# pcb10_13.net
KiCad netlist of a schematic drawn in EAGLE
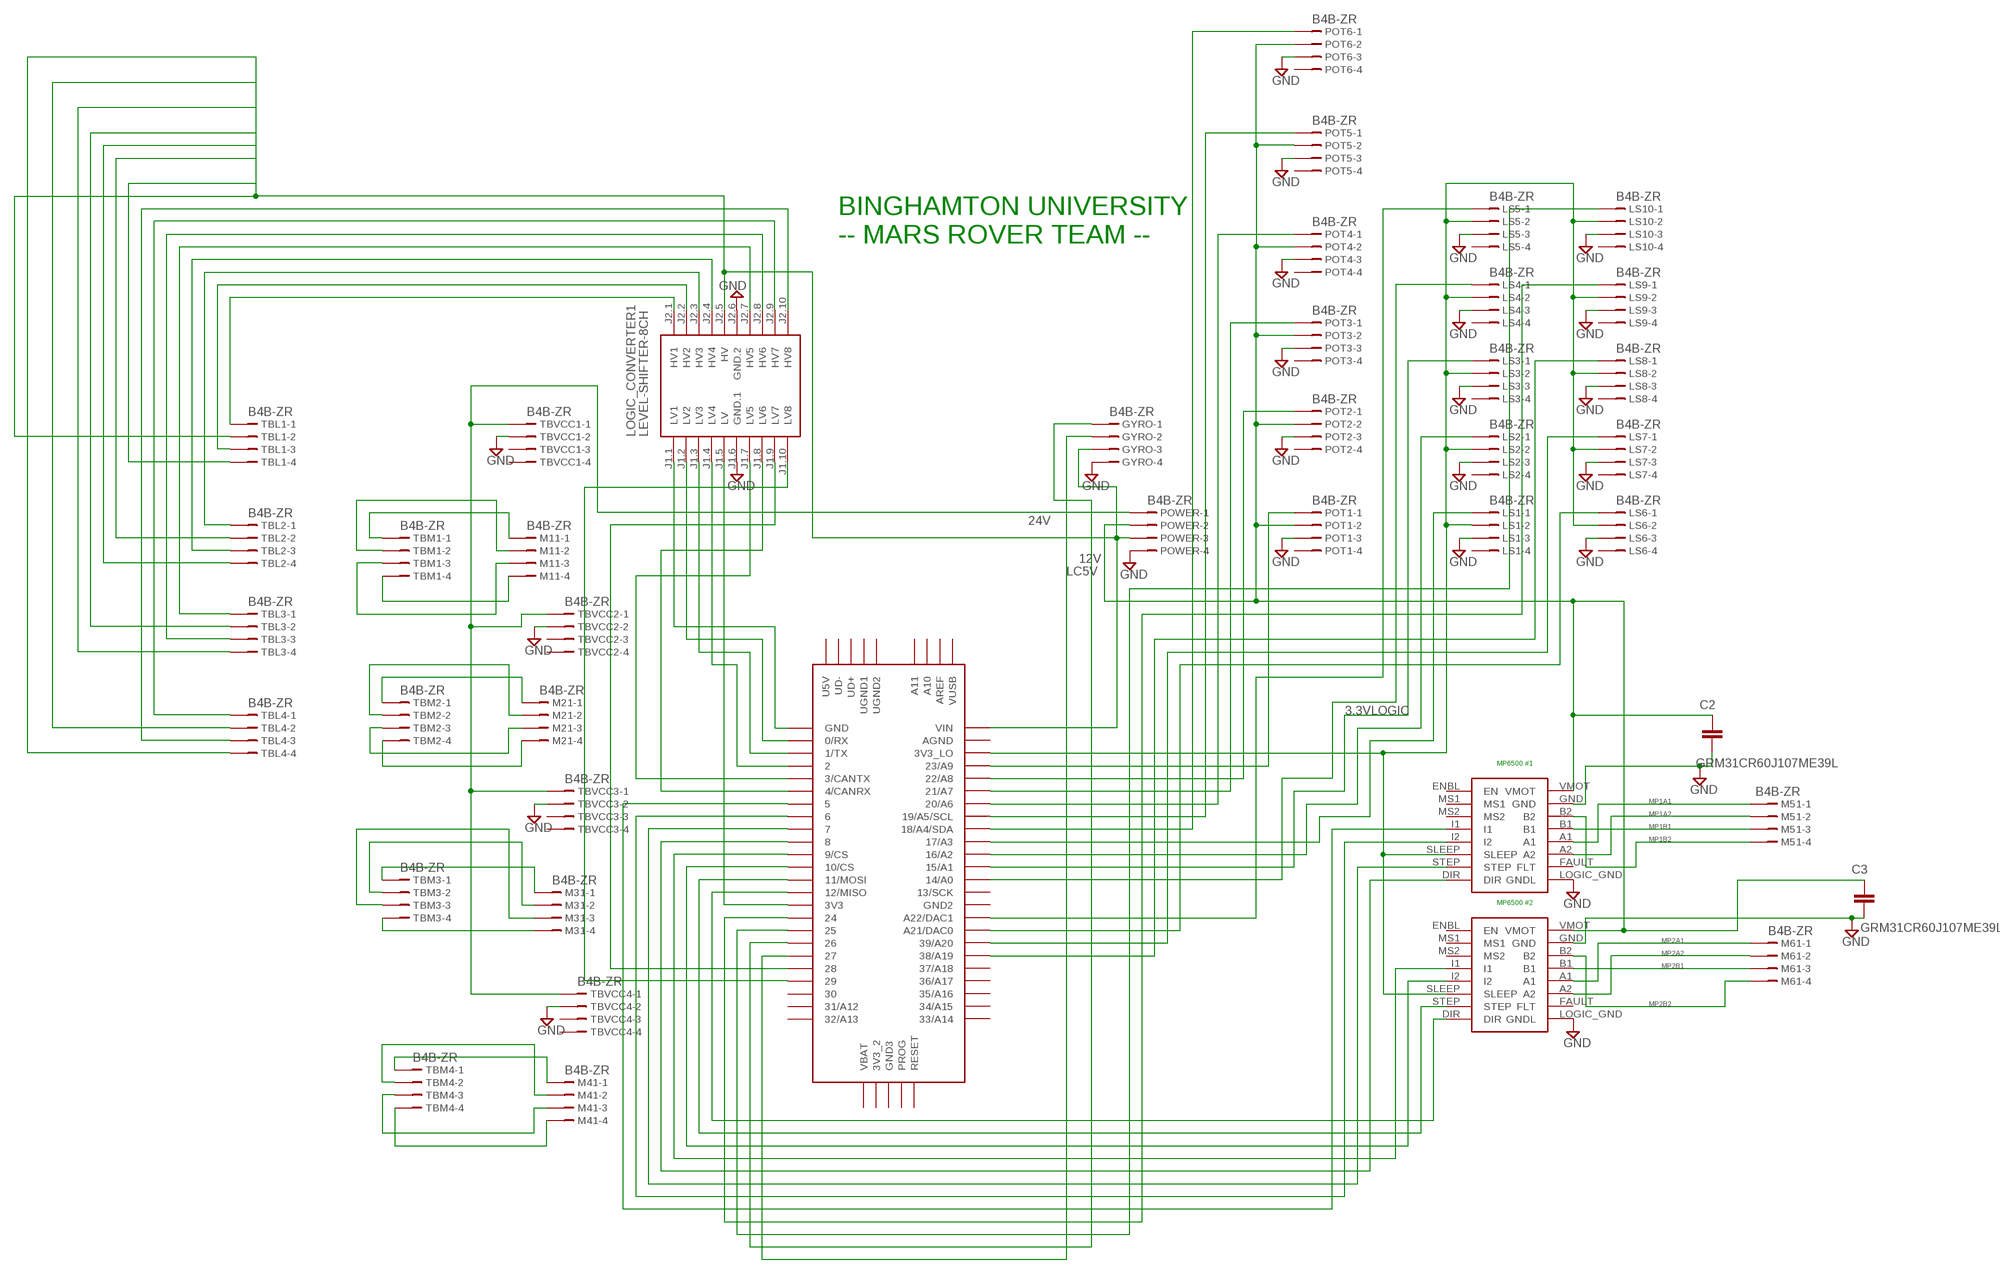
[diagram p0: schematic, sheet 1]

(export (version "E")
  (design (tool "Eeschema 10.0.6"))
  (components
    (comp (ref "C2")
      (value "GRM31CR60J107ME39L")
      (footprint "eagle-import:CAP_1206")
      (fields
        (field (name "MANUFACTURER") "Murata Electronics North America")
        (field (name "CREATED_BY") "PCBLayout.com")
      )
      (libsource (lib "eagle-import") (part "GRM31CR60J107ME39L"))
    )
    (comp (ref "C3")
      (value "GRM31CR60J107ME39L")
      (footprint "eagle-import:CAP_1206")
      (fields
        (field (name "MANUFACTURER") "Murata Electronics North America")
        (field (name "CREATED_BY") "PCBLayout.com")
      )
      (libsource (lib "eagle-import") (part "GRM31CR60J107ME39L"))
    )
    (comp (ref "GYRO")
      (value "B4B-ZR")
      (footprint "eagle-import:B4B-ZR")
      (fields (field (name "MF") "FARNELL") (field (name "MPN") "B4B-ZR(LF)(SN)"))
      (libsource (lib "eagle-import") (part "?4B-ZRB"))
    )
    (comp (ref "LOGIC_CONVERTER1")
      (value "LEVEL-SHIFTER-8CH")
      (footprint "eagle-import:LEVEL-SHIFTER-8CH")
      (libsource (lib "eagle-import") (part "LEVEL-SHIFTER-8CH"))
    )
    (comp (ref "LS1")
      (value "B4B-ZR")
      (footprint "eagle-import:B4B-ZR")
      (fields (field (name "MF") "FARNELL") (field (name "MPN") "B4B-ZR(LF)(SN)"))
      (libsource (lib "eagle-import") (part "?4B-ZRB"))
    )
    (comp (ref "LS2")
      (value "B4B-ZR")
      (footprint "eagle-import:B4B-ZR")
      (fields (field (name "MF") "FARNELL") (field (name "MPN") "B4B-ZR(LF)(SN)"))
      (libsource (lib "eagle-import") (part "?4B-ZRB"))
    )
    (comp (ref "LS3")
      (value "B4B-ZR")
      (footprint "eagle-import:B4B-ZR")
      (fields (field (name "MF") "FARNELL") (field (name "MPN") "B4B-ZR(LF)(SN)"))
      (libsource (lib "eagle-import") (part "?4B-ZRB"))
    )
    (comp (ref "LS4")
      (value "B4B-ZR")
      (footprint "eagle-import:B4B-ZR")
      (fields (field (name "MF") "FARNELL") (field (name "MPN") "B4B-ZR(LF)(SN)"))
      (libsource (lib "eagle-import") (part "?4B-ZRB"))
    )
    (comp (ref "LS5")
      (value "B4B-ZR")
      (footprint "eagle-import:B4B-ZR")
      (fields (field (name "MF") "FARNELL") (field (name "MPN") "B4B-ZR(LF)(SN)"))
      (libsource (lib "eagle-import") (part "?4B-ZRB"))
    )
    (comp (ref "LS6")
      (value "B4B-ZR")
      (footprint "eagle-import:B4B-ZR")
      (fields (field (name "MF") "FARNELL") (field (name "MPN") "B4B-ZR(LF)(SN)"))
      (libsource (lib "eagle-import") (part "?4B-ZRB"))
    )
    (comp (ref "LS7")
      (value "B4B-ZR")
      (footprint "eagle-import:B4B-ZR")
      (fields (field (name "MF") "FARNELL") (field (name "MPN") "B4B-ZR(LF)(SN)"))
      (libsource (lib "eagle-import") (part "?4B-ZRB"))
    )
    (comp (ref "LS8")
      (value "B4B-ZR")
      (footprint "eagle-import:B4B-ZR")
      (fields (field (name "MF") "FARNELL") (field (name "MPN") "B4B-ZR(LF)(SN)"))
      (libsource (lib "eagle-import") (part "?4B-ZRB"))
    )
    (comp (ref "LS9")
      (value "B4B-ZR")
      (footprint "eagle-import:B4B-ZR")
      (fields (field (name "MF") "FARNELL") (field (name "MPN") "B4B-ZR(LF)(SN)"))
      (libsource (lib "eagle-import") (part "?4B-ZRB"))
    )
    (comp (ref "LS10")
      (value "B4B-ZR")
      (footprint "eagle-import:B4B-ZR")
      (fields (field (name "MF") "FARNELL") (field (name "MPN") "B4B-ZR(LF)(SN)"))
      (libsource (lib "eagle-import") (part "?4B-ZRB"))
    )
    (comp (ref "M11")
      (value "B4B-ZR")
      (footprint "eagle-import:B4B-ZR")
      (fields (field (name "MF") "FARNELL") (field (name "MPN") "B4B-ZR(LF)(SN)"))
      (libsource (lib "eagle-import") (part "?4B-ZRB"))
    )
    (comp (ref "M21")
      (value "B4B-ZR")
      (footprint "eagle-import:B4B-ZR")
      (fields (field (name "MF") "FARNELL") (field (name "MPN") "B4B-ZR(LF)(SN)"))
      (libsource (lib "eagle-import") (part "?4B-ZRB"))
    )
    (comp (ref "M31")
      (value "B4B-ZR")
      (footprint "eagle-import:B4B-ZR")
      (fields (field (name "MF") "FARNELL") (field (name "MPN") "B4B-ZR(LF)(SN)"))
      (libsource (lib "eagle-import") (part "?4B-ZRB"))
    )
    (comp (ref "M41")
      (value "B4B-ZR")
      (footprint "eagle-import:B4B-ZR")
      (fields (field (name "MF") "FARNELL") (field (name "MPN") "B4B-ZR(LF)(SN)"))
      (libsource (lib "eagle-import") (part "?4B-ZRB"))
    )
    (comp (ref "M51")
      (value "B4B-ZR")
      (footprint "eagle-import:B4B-ZR")
      (fields (field (name "MF") "FARNELL") (field (name "MPN") "B4B-ZR(LF)(SN)"))
      (libsource (lib "eagle-import") (part "?4B-ZRB"))
    )
    (comp (ref "M61")
      (value "B4B-ZR")
      (footprint "eagle-import:B4B-ZR")
      (fields (field (name "MF") "FARNELL") (field (name "MPN") "B4B-ZR(LF)(SN)"))
      (libsource (lib "eagle-import") (part "?4B-ZRB"))
    )
    (comp (ref "MP6500_3")
      (value "MP6500THROUGH_HOLE")
      (footprint "eagle-import:MP6500")
      (libsource (lib "eagle-import") (part "MP6500THROUGH_HOLE"))
    )
    (comp (ref "MP6500_4")
      (value "MP6500THROUGH_HOLE")
      (footprint "eagle-import:MP6500")
      (libsource (lib "eagle-import") (part "MP6500THROUGH_HOLE"))
    )
    (comp (ref "POT1")
      (value "B4B-ZR")
      (footprint "eagle-import:B4B-ZR")
      (fields (field (name "MF") "FARNELL") (field (name "MPN") "B4B-ZR(LF)(SN)"))
      (libsource (lib "eagle-import") (part "?4B-ZRB"))
    )
    (comp (ref "POT2")
      (value "B4B-ZR")
      (footprint "eagle-import:B4B-ZR")
      (fields (field (name "MF") "FARNELL") (field (name "MPN") "B4B-ZR(LF)(SN)"))
      (libsource (lib "eagle-import") (part "?4B-ZRB"))
    )
    (comp (ref "POT3")
      (value "B4B-ZR")
      (footprint "eagle-import:B4B-ZR")
      (fields (field (name "MF") "FARNELL") (field (name "MPN") "B4B-ZR(LF)(SN)"))
      (libsource (lib "eagle-import") (part "?4B-ZRB"))
    )
    (comp (ref "POT4")
      (value "B4B-ZR")
      (footprint "eagle-import:B4B-ZR")
      (fields (field (name "MF") "FARNELL") (field (name "MPN") "B4B-ZR(LF)(SN)"))
      (libsource (lib "eagle-import") (part "?4B-ZRB"))
    )
    (comp (ref "POT5")
      (value "B4B-ZR")
      (footprint "eagle-import:B4B-ZR")
      (fields (field (name "MF") "FARNELL") (field (name "MPN") "B4B-ZR(LF)(SN)"))
      (libsource (lib "eagle-import") (part "?4B-ZRB"))
    )
    (comp (ref "POT6")
      (value "B4B-ZR")
      (footprint "eagle-import:B4B-ZR")
      (fields (field (name "MF") "FARNELL") (field (name "MPN") "B4B-ZR(LF)(SN)"))
      (libsource (lib "eagle-import") (part "?4B-ZRB"))
    )
    (comp (ref "POWER")
      (value "B4B-ZR")
      (footprint "eagle-import:B4B-ZR")
      (fields (field (name "MF") "FARNELL") (field (name "MPN") "B4B-ZR(LF)(SN)"))
      (libsource (lib "eagle-import") (part "?4B-ZRB"))
    )
    (comp (ref "TBL1")
      (value "B4B-ZR")
      (footprint "eagle-import:B4B-ZR")
      (fields (field (name "MF") "FARNELL") (field (name "MPN") "B4B-ZR(LF)(SN)"))
      (libsource (lib "eagle-import") (part "?4B-ZRB"))
    )
    (comp (ref "TBL2")
      (value "B4B-ZR")
      (footprint "eagle-import:B4B-ZR")
      (fields (field (name "MF") "FARNELL") (field (name "MPN") "B4B-ZR(LF)(SN)"))
      (libsource (lib "eagle-import") (part "?4B-ZRB"))
    )
    (comp (ref "TBL3")
      (value "B4B-ZR")
      (footprint "eagle-import:B4B-ZR")
      (fields (field (name "MF") "FARNELL") (field (name "MPN") "B4B-ZR(LF)(SN)"))
      (libsource (lib "eagle-import") (part "?4B-ZRB"))
    )
    (comp (ref "TBL4")
      (value "B4B-ZR")
      (footprint "eagle-import:B4B-ZR")
      (fields (field (name "MF") "FARNELL") (field (name "MPN") "B4B-ZR(LF)(SN)"))
      (libsource (lib "eagle-import") (part "?4B-ZRB"))
    )
    (comp (ref "TBM1")
      (value "B4B-ZR")
      (footprint "eagle-import:B4B-ZR")
      (fields (field (name "MF") "FARNELL") (field (name "MPN") "B4B-ZR(LF)(SN)"))
      (libsource (lib "eagle-import") (part "?4B-ZRB"))
    )
    (comp (ref "TBM2")
      (value "B4B-ZR")
      (footprint "eagle-import:B4B-ZR")
      (fields (field (name "MF") "FARNELL") (field (name "MPN") "B4B-ZR(LF)(SN)"))
      (libsource (lib "eagle-import") (part "?4B-ZRB"))
    )
    (comp (ref "TBM3")
      (value "B4B-ZR")
      (footprint "eagle-import:B4B-ZR")
      (fields (field (name "MF") "FARNELL") (field (name "MPN") "B4B-ZR(LF)(SN)"))
      (libsource (lib "eagle-import") (part "?4B-ZRB"))
    )
    (comp (ref "TBM4")
      (value "B4B-ZR")
      (footprint "eagle-import:B4B-ZR")
      (fields (field (name "MF") "FARNELL") (field (name "MPN") "B4B-ZR(LF)(SN)"))
      (libsource (lib "eagle-import") (part "?4B-ZRB"))
    )
    (comp (ref "TBVCC1")
      (value "B4B-ZR")
      (footprint "eagle-import:B4B-ZR")
      (fields (field (name "MF") "FARNELL") (field (name "MPN") "B4B-ZR(LF)(SN)"))
      (libsource (lib "eagle-import") (part "?4B-ZRB"))
    )
    (comp (ref "TBVCC2")
      (value "B4B-ZR")
      (footprint "eagle-import:B4B-ZR")
      (fields (field (name "MF") "FARNELL") (field (name "MPN") "B4B-ZR(LF)(SN)"))
      (libsource (lib "eagle-import") (part "?4B-ZRB"))
    )
    (comp (ref "TBVCC3")
      (value "B4B-ZR")
      (footprint "eagle-import:B4B-ZR")
      (fields (field (name "MF") "FARNELL") (field (name "MPN") "B4B-ZR(LF)(SN)"))
      (libsource (lib "eagle-import") (part "?4B-ZRB"))
    )
    (comp (ref "TBVCC4")
      (value "B4B-ZR")
      (footprint "eagle-import:B4B-ZR")
      (fields (field (name "MF") "FARNELL") (field (name "MPN") "B4B-ZR(LF)(SN)"))
      (libsource (lib "eagle-import") (part "?4B-ZRB"))
    )
    (comp (ref "TEENSY4.2")
      (value "TEENSY_3.5/3.6")
      (footprint "eagle-import:TEENSY_3.5_3.6")
      (libsource (lib "eagle-import") (part "TEENSY_3.5/3.6"))
    )
  )
  (nets
    (net (code "1") (name "/3.3VLOGIC") (class "Default")
      (node (ref "LS1") (pin "2") (pinfunction "1_2") (pintype "passive"))
      (node (ref "LS10") (pin "2") (pinfunction "1_2") (pintype "passive"))
      (node (ref "LS2") (pin "2") (pinfunction "1_2") (pintype "passive"))
      (node (ref "LS3") (pin "2") (pinfunction "1_2") (pintype "passive"))
      (node (ref "LS4") (pin "2") (pinfunction "1_2") (pintype "passive"))
      (node (ref "LS5") (pin "2") (pinfunction "1_2") (pintype "passive"))
      (node (ref "LS6") (pin "2") (pinfunction "1_2") (pintype "passive"))
      (node (ref "LS7") (pin "2") (pinfunction "1_2") (pintype "passive"))
      (node (ref "LS8") (pin "2") (pinfunction "1_2") (pintype "passive"))
      (node (ref "LS9") (pin "2") (pinfunction "1_2") (pintype "passive"))
      (node (ref "MP6500_3") (pin "SLEEP") (pinfunction "SLEEP_SLEEP") (pintype "bidirectional"))
      (node (ref "MP6500_4") (pin "SLEEP") (pinfunction "SLEEP_SLEEP") (pintype "bidirectional"))
      (node (ref "TEENSY4.2") (pin "3V3_LO") (pinfunction "3V3_LO_3V3_LO") (pintype "bidirectional"))
    )
    (net (code "2") (name "/12V") (class "Default")
      (node (ref "C2") (pin "1") (pinfunction "1_1") (pintype "passive"))
      (node (ref "C3") (pin "1") (pinfunction "1_1") (pintype "passive"))
      (node (ref "MP6500_3") (pin "VMOT") (pinfunction "VMOT_VMOT") (pintype "bidirectional"))
      (node (ref "MP6500_4") (pin "VMOT") (pinfunction "VMOT_VMOT") (pintype "bidirectional"))
      (node (ref "POT1") (pin "2") (pinfunction "1_2") (pintype "passive"))
      (node (ref "POT2") (pin "2") (pinfunction "1_2") (pintype "passive"))
      (node (ref "POT3") (pin "2") (pinfunction "1_2") (pintype "passive"))
      (node (ref "POT4") (pin "2") (pinfunction "1_2") (pintype "passive"))
      (node (ref "POT5") (pin "2") (pinfunction "1_2") (pintype "passive"))
      (node (ref "POT6") (pin "2") (pinfunction "1_2") (pintype "passive"))
      (node (ref "POWER") (pin "2") (pinfunction "1_2") (pintype "passive"))
    )
    (net (code "3") (name "/24V") (class "Default")
      (node (ref "POWER") (pin "1") (pinfunction "1_1") (pintype "passive"))
      (node (ref "TBVCC1") (pin "1") (pinfunction "1_1") (pintype "passive"))
      (node (ref "TBVCC2") (pin "1") (pinfunction "1_1") (pintype "passive"))
      (node (ref "TBVCC3") (pin "1") (pinfunction "1_1") (pintype "passive"))
      (node (ref "TBVCC4") (pin "1") (pinfunction "1_1") (pintype "passive"))
    )
    (net (code "4") (name "/LC5V") (class "Default")
      (node (ref "GYRO") (pin "3") (pinfunction "1_3") (pintype "passive"))
      (node (ref "LOGIC_CONVERTER1") (pin "J2.5") (pinfunction "HV_J2.5") (pintype "power_in"))
      (node (ref "POWER") (pin "3") (pinfunction "1_3") (pintype "passive"))
      (node (ref "TBL1") (pin "2") (pinfunction "1_2") (pintype "passive"))
      (node (ref "TBL1") (pin "4") (pinfunction "1_4") (pintype "passive"))
      (node (ref "TBL2") (pin "2") (pinfunction "1_2") (pintype "passive"))
      (node (ref "TBL2") (pin "4") (pinfunction "1_4") (pintype "passive"))
      (node (ref "TBL3") (pin "2") (pinfunction "1_2") (pintype "passive"))
      (node (ref "TBL3") (pin "4") (pinfunction "1_4") (pintype "passive"))
      (node (ref "TBL4") (pin "2") (pinfunction "1_2") (pintype "passive"))
      (node (ref "TBL4") (pin "4") (pinfunction "1_4") (pintype "passive"))
      (node (ref "TEENSY4.2") (pin "VIN") (pinfunction "VIN_VIN") (pintype "bidirectional"))
    )
    (net (code "5") (name "/MP1A1") (class "Default")
      (node (ref "M51") (pin "1") (pinfunction "1_1") (pintype "passive"))
      (node (ref "MP6500_3") (pin "A1") (pinfunction "A1_A1") (pintype "bidirectional"))
    )
    (net (code "6") (name "/MP1A2") (class "Default")
      (node (ref "M51") (pin "2") (pinfunction "1_2") (pintype "passive"))
      (node (ref "MP6500_3") (pin "A2") (pinfunction "A2_A2") (pintype "bidirectional"))
    )
    (net (code "7") (name "/MP1B1") (class "Default")
      (node (ref "M51") (pin "3") (pinfunction "1_3") (pintype "passive"))
      (node (ref "MP6500_3") (pin "B1") (pinfunction "B1_B1") (pintype "bidirectional"))
    )
    (net (code "8") (name "/MP1B2") (class "Default")
      (node (ref "M51") (pin "4") (pinfunction "1_4") (pintype "passive"))
      (node (ref "MP6500_3") (pin "B2") (pinfunction "B2_B2") (pintype "bidirectional"))
    )
    (net (code "9") (name "/MP2A1") (class "Default")
      (node (ref "M61") (pin "1") (pinfunction "1_1") (pintype "passive"))
      (node (ref "MP6500_4") (pin "A1") (pinfunction "A1_A1") (pintype "bidirectional"))
    )
    (net (code "10") (name "/MP2A2") (class "Default")
      (node (ref "M61") (pin "2") (pinfunction "1_2") (pintype "passive"))
      (node (ref "MP6500_4") (pin "A2") (pinfunction "A2_A2") (pintype "bidirectional"))
    )
    (net (code "11") (name "/MP2B1") (class "Default")
      (node (ref "M61") (pin "3") (pinfunction "1_3") (pintype "passive"))
      (node (ref "MP6500_4") (pin "B1") (pinfunction "B1_B1") (pintype "bidirectional"))
    )
    (net (code "12") (name "/MP2B2") (class "Default")
      (node (ref "M61") (pin "4") (pinfunction "1_4") (pintype "passive"))
      (node (ref "MP6500_4") (pin "B2") (pinfunction "B2_B2") (pintype "bidirectional"))
    )
    (net (code "13") (name "GND") (class "Default")
      (node (ref "C2") (pin "2") (pinfunction "2_2") (pintype "passive"))
      (node (ref "C3") (pin "2") (pinfunction "2_2") (pintype "passive"))
      (node (ref "GYRO") (pin "4") (pinfunction "1_4") (pintype "passive"))
      (node (ref "LOGIC_CONVERTER1") (pin "J1.6") (pinfunction "GND.1_J1.6") (pintype "power_in"))
      (node (ref "LOGIC_CONVERTER1") (pin "J2.6") (pinfunction "GND.2_J2.6") (pintype "power_in"))
      (node (ref "LS1") (pin "3") (pinfunction "1_3") (pintype "passive"))
      (node (ref "LS10") (pin "3") (pinfunction "1_3") (pintype "passive"))
      (node (ref "LS2") (pin "3") (pinfunction "1_3") (pintype "passive"))
      (node (ref "LS3") (pin "3") (pinfunction "1_3") (pintype "passive"))
      (node (ref "LS4") (pin "3") (pinfunction "1_3") (pintype "passive"))
      (node (ref "LS5") (pin "3") (pinfunction "1_3") (pintype "passive"))
      (node (ref "LS6") (pin "3") (pinfunction "1_3") (pintype "passive"))
      (node (ref "LS7") (pin "3") (pinfunction "1_3") (pintype "passive"))
      (node (ref "LS8") (pin "3") (pinfunction "1_3") (pintype "passive"))
      (node (ref "LS9") (pin "3") (pinfunction "1_3") (pintype "passive"))
      (node (ref "MP6500_3") (pin "GND") (pinfunction "GND_GND") (pintype "bidirectional"))
      (node (ref "MP6500_3") (pin "LOGIC_GND") (pinfunction "GNDL_LOGIC_GND") (pintype "bidirectional"))
      (node (ref "MP6500_4") (pin "GND") (pinfunction "GND_GND") (pintype "bidirectional"))
      (node (ref "MP6500_4") (pin "LOGIC_GND") (pinfunction "GNDL_LOGIC_GND") (pintype "bidirectional"))
      (node (ref "POT1") (pin "3") (pinfunction "1_3") (pintype "passive"))
      (node (ref "POT2") (pin "3") (pinfunction "1_3") (pintype "passive"))
      (node (ref "POT3") (pin "3") (pinfunction "1_3") (pintype "passive"))
      (node (ref "POT4") (pin "3") (pinfunction "1_3") (pintype "passive"))
      (node (ref "POT5") (pin "3") (pinfunction "1_3") (pintype "passive"))
      (node (ref "POT6") (pin "3") (pinfunction "1_3") (pintype "passive"))
      (node (ref "POWER") (pin "4") (pinfunction "1_4") (pintype "passive"))
      (node (ref "TBVCC1") (pin "2") (pinfunction "1_2") (pintype "passive"))
      (node (ref "TBVCC2") (pin "2") (pinfunction "1_2") (pintype "passive"))
      (node (ref "TBVCC3") (pin "2") (pinfunction "1_2") (pintype "passive"))
      (node (ref "TBVCC4") (pin "2") (pinfunction "1_2") (pintype "passive"))
    )
    (net (code "14") (name "Net-(GYRO-Pad1)") (class "Default")
      (node (ref "GYRO") (pin "1") (pinfunction "1_1") (pintype "passive"))
      (node (ref "TEENSY4.2") (pin "26") (pinfunction "26_26") (pintype "bidirectional"))
    )
    (net (code "15") (name "Net-(GYROB-1)") (class "Default")
      (node (ref "GYRO") (pin "2") (pinfunction "1_2") (pintype "passive"))
      (node (ref "TEENSY4.2") (pin "27") (pinfunction "27_27") (pintype "bidirectional"))
    )
    (net (code "16") (name "Net-(LOGIC_CONVERTER1-HV1)") (class "Default")
      (node (ref "LOGIC_CONVERTER1") (pin "J2.1") (pinfunction "HV1_J2.1") (pintype "bidirectional"))
      (node (ref "TBL1") (pin "1") (pinfunction "1_1") (pintype "passive"))
    )
    (net (code "17") (name "Net-(LOGIC_CONVERTER1-HV2)") (class "Default")
      (node (ref "LOGIC_CONVERTER1") (pin "J2.2") (pinfunction "HV2_J2.2") (pintype "bidirectional"))
      (node (ref "TBL1") (pin "3") (pinfunction "1_3") (pintype "passive"))
    )
    (net (code "18") (name "Net-(LOGIC_CONVERTER1-HV3)") (class "Default")
      (node (ref "LOGIC_CONVERTER1") (pin "J2.3") (pinfunction "HV3_J2.3") (pintype "bidirectional"))
      (node (ref "TBL2") (pin "1") (pinfunction "1_1") (pintype "passive"))
    )
    (net (code "19") (name "Net-(LOGIC_CONVERTER1-HV4)") (class "Default")
      (node (ref "LOGIC_CONVERTER1") (pin "J2.4") (pinfunction "HV4_J2.4") (pintype "bidirectional"))
      (node (ref "TBL2") (pin "3") (pinfunction "1_3") (pintype "passive"))
    )
    (net (code "20") (name "Net-(LOGIC_CONVERTER1-HV5)") (class "Default")
      (node (ref "LOGIC_CONVERTER1") (pin "J2.7") (pinfunction "HV5_J2.7") (pintype "bidirectional"))
      (node (ref "TBL3") (pin "1") (pinfunction "1_1") (pintype "passive"))
    )
    (net (code "21") (name "Net-(LOGIC_CONVERTER1-HV6)") (class "Default")
      (node (ref "LOGIC_CONVERTER1") (pin "J2.8") (pinfunction "HV6_J2.8") (pintype "bidirectional"))
      (node (ref "TBL3") (pin "3") (pinfunction "1_3") (pintype "passive"))
    )
    (net (code "22") (name "Net-(LOGIC_CONVERTER1-HV7)") (class "Default")
      (node (ref "LOGIC_CONVERTER1") (pin "J2.9") (pinfunction "HV7_J2.9") (pintype "bidirectional"))
      (node (ref "TBL4") (pin "1") (pinfunction "1_1") (pintype "passive"))
    )
    (net (code "23") (name "Net-(LOGIC_CONVERTER1-HV8)") (class "Default")
      (node (ref "LOGIC_CONVERTER1") (pin "J2.10") (pinfunction "HV8_J2.10") (pintype "bidirectional"))
      (node (ref "TBL4") (pin "3") (pinfunction "1_3") (pintype "passive"))
    )
    (net (code "24") (name "Net-(LOGIC_CONVERTER1-LV)") (class "Default")
      (node (ref "LOGIC_CONVERTER1") (pin "J1.5") (pinfunction "LV_J1.5") (pintype "power_in"))
      (node (ref "TEENSY4.2") (pin "3V3") (pinfunction "3V3_3V3") (pintype "bidirectional"))
    )
    (net (code "25") (name "Net-(LOGIC_CONVERTER1-LV1)") (class "Default")
      (node (ref "LOGIC_CONVERTER1") (pin "J1.1") (pinfunction "LV1_J1.1") (pintype "bidirectional"))
      (node (ref "TEENSY4.2") (pin "GND") (pinfunction "GND_GND") (pintype "bidirectional"))
    )
    (net (code "26") (name "Net-(LOGIC_CONVERTER1-LV2)") (class "Default")
      (node (ref "LOGIC_CONVERTER1") (pin "J1.2") (pinfunction "LV2_J1.2") (pintype "bidirectional"))
      (node (ref "TEENSY4.2") (pin "0/RX") (pinfunction "0/RX_0/RX") (pintype "bidirectional"))
    )
    (net (code "27") (name "Net-(LOGIC_CONVERTER1-LV3)") (class "Default")
      (node (ref "LOGIC_CONVERTER1") (pin "J1.3") (pinfunction "LV3_J1.3") (pintype "bidirectional"))
      (node (ref "TEENSY4.2") (pin "1/TX") (pinfunction "1/TX_1/TX") (pintype "bidirectional"))
    )
    (net (code "28") (name "Net-(LOGIC_CONVERTER1-LV4)") (class "Default")
      (node (ref "LOGIC_CONVERTER1") (pin "J1.4") (pinfunction "LV4_J1.4") (pintype "bidirectional"))
      (node (ref "TEENSY4.2") (pin "2") (pinfunction "2_2") (pintype "bidirectional"))
    )
    (net (code "29") (name "Net-(LOGIC_CONVERTER1-LV5)") (class "Default")
      (node (ref "LOGIC_CONVERTER1") (pin "J1.7") (pinfunction "LV5_J1.7") (pintype "bidirectional"))
      (node (ref "TEENSY4.2") (pin "3/CANTX") (pinfunction "3/CANTX_3/CANTX") (pintype "bidirectional"))
    )
    (net (code "30") (name "Net-(LOGIC_CONVERTER1-LV6)") (class "Default")
      (node (ref "LOGIC_CONVERTER1") (pin "J1.8") (pinfunction "LV6_J1.8") (pintype "bidirectional"))
      (node (ref "TEENSY4.2") (pin "4/CANRX") (pinfunction "4/CANRX_4/CANRX") (pintype "bidirectional"))
    )
    (net (code "31") (name "Net-(LOGIC_CONVERTER1-LV7)") (class "Default")
      (node (ref "LOGIC_CONVERTER1") (pin "J1.9") (pinfunction "LV7_J1.9") (pintype "bidirectional"))
      (node (ref "TEENSY4.2") (pin "28") (pinfunction "28_28") (pintype "bidirectional"))
    )
    (net (code "32") (name "Net-(LOGIC_CONVERTER1-LV8)") (class "Default")
      (node (ref "LOGIC_CONVERTER1") (pin "J1.10") (pinfunction "LV8_J1.10") (pintype "bidirectional"))
      (node (ref "TEENSY4.2") (pin "29") (pinfunction "29_29") (pintype "bidirectional"))
    )
    (net (code "33") (name "Net-(LS1-Pad1)") (class "Default")
      (node (ref "LS1") (pin "1") (pinfunction "1_1") (pintype "passive"))
      (node (ref "TEENSY4.2") (pin "17/A3") (pinfunction "17/A3_17/A3") (pintype "bidirectional"))
    )
    (net (code "34") (name "Net-(LS2-Pad1)") (class "Default")
      (node (ref "LS2") (pin "1") (pinfunction "1_1") (pintype "passive"))
      (node (ref "TEENSY4.2") (pin "16/A2") (pinfunction "16/A2_16/A2") (pintype "bidirectional"))
    )
    (net (code "35") (name "Net-(LS3-Pad1)") (class "Default")
      (node (ref "LS3") (pin "1") (pinfunction "1_1") (pintype "passive"))
      (node (ref "TEENSY4.2") (pin "15/A1") (pinfunction "15/A1_15/A1") (pintype "bidirectional"))
    )
    (net (code "36") (name "Net-(LS4-Pad1)") (class "Default")
      (node (ref "LS4") (pin "1") (pinfunction "1_1") (pintype "passive"))
      (node (ref "TEENSY4.2") (pin "14/A0") (pinfunction "14/A0_14/A0") (pintype "bidirectional"))
    )
    (net (code "37") (name "Net-(LS5-Pad1)") (class "Default")
      (node (ref "LS5") (pin "1") (pinfunction "1_1") (pintype "passive"))
      (node (ref "TEENSY4.2") (pin "A22/DAC1") (pinfunction "A22/DAC1_A22/DAC1") (pintype "bidirectional"))
    )
    (net (code "38") (name "Net-(LS7-Pad1)") (class "Default")
      (node (ref "LS7") (pin "1") (pinfunction "1_1") (pintype "passive"))
      (node (ref "TEENSY4.2") (pin "39/A20") (pinfunction "39/A20_39/A20") (pintype "bidirectional"))
    )
    (net (code "39") (name "Net-(LS8-Pad1)") (class "Default")
      (node (ref "LS8") (pin "1") (pinfunction "1_1") (pintype "passive"))
      (node (ref "TEENSY4.2") (pin "38/A19") (pinfunction "38/A19_38/A19") (pintype "bidirectional"))
    )
    (net (code "40") (name "Net-(LS9-Pad1)") (class "Default")
      (node (ref "LS9") (pin "1") (pinfunction "1_1") (pintype "passive"))
      (node (ref "TEENSY4.2") (pin "24") (pinfunction "24_24") (pintype "bidirectional"))
    )
    (net (code "41") (name "Net-(LS10-Pad1)") (class "Default")
      (node (ref "LS10") (pin "1") (pinfunction "1_1") (pintype "passive"))
      (node (ref "TEENSY4.2") (pin "25") (pinfunction "25_25") (pintype "bidirectional"))
    )
    (net (code "42") (name "Net-(M11-Pad1)") (class "Default")
      (node (ref "M11") (pin "1") (pinfunction "1_1") (pintype "passive"))
      (node (ref "TBM1") (pin "1") (pinfunction "1_1") (pintype "passive"))
    )
    (net (code "43") (name "Net-(M11B-1)") (class "Default")
      (node (ref "M11") (pin "2") (pinfunction "1_2") (pintype "passive"))
      (node (ref "TBM1") (pin "2") (pinfunction "1_2") (pintype "passive"))
    )
    (net (code "44") (name "Net-(M11C-1)") (class "Default")
      (node (ref "M11") (pin "3") (pinfunction "1_3") (pintype "passive"))
      (node (ref "TBM1") (pin "3") (pinfunction "1_3") (pintype "passive"))
    )
    (net (code "45") (name "Net-(M11D-1)") (class "Default")
      (node (ref "M11") (pin "4") (pinfunction "1_4") (pintype "passive"))
      (node (ref "TBM1") (pin "4") (pinfunction "1_4") (pintype "passive"))
    )
    (net (code "46") (name "Net-(M21-Pad1)") (class "Default")
      (node (ref "M21") (pin "1") (pinfunction "1_1") (pintype "passive"))
      (node (ref "TBM2") (pin "1") (pinfunction "1_1") (pintype "passive"))
    )
    (net (code "47") (name "Net-(M21B-1)") (class "Default")
      (node (ref "M21") (pin "2") (pinfunction "1_2") (pintype "passive"))
      (node (ref "TBM2") (pin "2") (pinfunction "1_2") (pintype "passive"))
    )
    (net (code "48") (name "Net-(M21C-1)") (class "Default")
      (node (ref "M21") (pin "3") (pinfunction "1_3") (pintype "passive"))
      (node (ref "TBM2") (pin "3") (pinfunction "1_3") (pintype "passive"))
    )
    (net (code "49") (name "Net-(M21D-1)") (class "Default")
      (node (ref "M21") (pin "4") (pinfunction "1_4") (pintype "passive"))
      (node (ref "TBM2") (pin "4") (pinfunction "1_4") (pintype "passive"))
    )
    (net (code "50") (name "Net-(M31-Pad1)") (class "Default")
      (node (ref "M31") (pin "1") (pinfunction "1_1") (pintype "passive"))
      (node (ref "TBM3") (pin "1") (pinfunction "1_1") (pintype "passive"))
    )
    (net (code "51") (name "Net-(M31B-1)") (class "Default")
      (node (ref "M31") (pin "2") (pinfunction "1_2") (pintype "passive"))
      (node (ref "TBM3") (pin "2") (pinfunction "1_2") (pintype "passive"))
    )
    (net (code "52") (name "Net-(M31C-1)") (class "Default")
      (node (ref "M31") (pin "3") (pinfunction "1_3") (pintype "passive"))
      (node (ref "TBM3") (pin "3") (pinfunction "1_3") (pintype "passive"))
    )
    (net (code "53") (name "Net-(M31D-1)") (class "Default")
      (node (ref "M31") (pin "4") (pinfunction "1_4") (pintype "passive"))
      (node (ref "TBM3") (pin "4") (pinfunction "1_4") (pintype "passive"))
    )
    (net (code "54") (name "Net-(M41-Pad1)") (class "Default")
      (node (ref "M41") (pin "1") (pinfunction "1_1") (pintype "passive"))
      (node (ref "TBM4") (pin "1") (pinfunction "1_1") (pintype "passive"))
    )
    (net (code "55") (name "Net-(M41B-1)") (class "Default")
      (node (ref "M41") (pin "2") (pinfunction "1_2") (pintype "passive"))
      (node (ref "TBM4") (pin "2") (pinfunction "1_2") (pintype "passive"))
    )
    (net (code "56") (name "Net-(M41C-1)") (class "Default")
      (node (ref "M41") (pin "3") (pinfunction "1_3") (pintype "passive"))
      (node (ref "TBM4") (pin "3") (pinfunction "1_3") (pintype "passive"))
    )
    (net (code "57") (name "Net-(M41D-1)") (class "Default")
      (node (ref "M41") (pin "4") (pinfunction "1_4") (pintype "passive"))
      (node (ref "TBM4") (pin "4") (pinfunction "1_4") (pintype "passive"))
    )
    (net (code "58") (name "Net-(MP6500_3-PadDIR)") (class "Default")
      (node (ref "MP6500_3") (pin "DIR") (pinfunction "DIR_DIR") (pintype "bidirectional"))
      (node (ref "TEENSY4.2") (pin "8") (pinfunction "8_8") (pintype "bidirectional"))
    )
    (net (code "59") (name "Net-(MP6500_3-PadI1)") (class "Default")
      (node (ref "MP6500_3") (pin "I1") (pinfunction "I1_I1") (pintype "bidirectional"))
      (node (ref "TEENSY4.2") (pin "5") (pinfunction "5_5") (pintype "bidirectional"))
    )
    (net (code "60") (name "Net-(MP6500_3-PadI2)") (class "Default")
      (node (ref "MP6500_3") (pin "I2") (pinfunction "I2_I2") (pintype "bidirectional"))
      (node (ref "TEENSY4.2") (pin "6") (pinfunction "6_6") (pintype "bidirectional"))
    )
    (net (code "61") (name "Net-(MP6500_3-PadSTEP)") (class "Default")
      (node (ref "MP6500_3") (pin "STEP") (pinfunction "STEP_STEP") (pintype "bidirectional"))
      (node (ref "TEENSY4.2") (pin "7") (pinfunction "7_7") (pintype "bidirectional"))
    )
    (net (code "62") (name "Net-(MP6500_4-PadDIR)") (class "Default")
      (node (ref "MP6500_4") (pin "DIR") (pinfunction "DIR_DIR") (pintype "bidirectional"))
      (node (ref "TEENSY4.2") (pin "12/MISO") (pinfunction "12/MISO_12/MISO") (pintype "bidirectional"))
    )
    (net (code "63") (name "Net-(MP6500_4-PadI1)") (class "Default")
      (node (ref "MP6500_4") (pin "I1") (pinfunction "I1_I1") (pintype "bidirectional"))
      (node (ref "TEENSY4.2") (pin "9/CS") (pinfunction "9/CS_9/CS") (pintype "bidirectional"))
    )
    (net (code "64") (name "Net-(MP6500_4-PadI2)") (class "Default")
      (node (ref "MP6500_4") (pin "I2") (pinfunction "I2_I2") (pintype "bidirectional"))
      (node (ref "TEENSY4.2") (pin "10/CS") (pinfunction "10/CS_10/CS") (pintype "bidirectional"))
    )
    (net (code "65") (name "Net-(MP6500_4-PadSTEP)") (class "Default")
      (node (ref "MP6500_4") (pin "STEP") (pinfunction "STEP_STEP") (pintype "bidirectional"))
      (node (ref "TEENSY4.2") (pin "11/MOSI") (pinfunction "11/MOSI_11/MOSI") (pintype "bidirectional"))
    )
    (net (code "66") (name "Net-(POT1-Pad1)") (class "Default")
      (node (ref "POT1") (pin "1") (pinfunction "1_1") (pintype "passive"))
      (node (ref "TEENSY4.2") (pin "23/A9") (pinfunction "23/A9_23/A9") (pintype "bidirectional"))
    )
    (net (code "67") (name "Net-(POT2-Pad1)") (class "Default")
      (node (ref "POT2") (pin "1") (pinfunction "1_1") (pintype "passive"))
      (node (ref "TEENSY4.2") (pin "22/A8") (pinfunction "22/A8_22/A8") (pintype "bidirectional"))
    )
    (net (code "68") (name "Net-(POT3-Pad1)") (class "Default")
      (node (ref "POT3") (pin "1") (pinfunction "1_1") (pintype "passive"))
      (node (ref "TEENSY4.2") (pin "21/A7") (pinfunction "21/A7_21/A7") (pintype "bidirectional"))
    )
    (net (code "69") (name "Net-(POT4-Pad1)") (class "Default")
      (node (ref "POT4") (pin "1") (pinfunction "1_1") (pintype "passive"))
      (node (ref "TEENSY4.2") (pin "20/A6") (pinfunction "20/A6_20/A6") (pintype "bidirectional"))
    )
    (net (code "70") (name "Net-(POT5-Pad1)") (class "Default")
      (node (ref "POT5") (pin "1") (pinfunction "1_1") (pintype "passive"))
      (node (ref "TEENSY4.2") (pin "19/A5/SCL") (pinfunction "19/A5/SCL_19/A5/SCL") (pintype "bidirectional"))
    )
    (net (code "71") (name "Net-(POT6-Pad1)") (class "Default")
      (node (ref "POT6") (pin "1") (pinfunction "1_1") (pintype "passive"))
      (node (ref "TEENSY4.2") (pin "18/A4/SDA") (pinfunction "18/A4/SDA_18/A4/SDA") (pintype "bidirectional"))
    )
    (net (code "72") (name "Net-(TEENSY4.2-A21{slash}DAC0)") (class "Default")
      (node (ref "LS6") (pin "1") (pinfunction "1_1") (pintype "passive"))
      (node (ref "TEENSY4.2") (pin "21/DAC0") (pinfunction "A21/DAC0_21/DAC0") (pintype "bidirectional"))
    )
    (net (code "73") (name "unconnected-(LS1D-1-Pad4)") (class "Default")
      (node (ref "LS1") (pin "4") (pinfunction "1_4") (pintype "passive"))
    )
    (net (code "74") (name "unconnected-(LS2D-1-Pad4)") (class "Default")
      (node (ref "LS2") (pin "4") (pinfunction "1_4") (pintype "passive"))
    )
    (net (code "75") (name "unconnected-(LS3D-1-Pad4)") (class "Default")
      (node (ref "LS3") (pin "4") (pinfunction "1_4") (pintype "passive"))
    )
    (net (code "76") (name "unconnected-(LS4D-1-Pad4)") (class "Default")
      (node (ref "LS4") (pin "4") (pinfunction "1_4") (pintype "passive"))
    )
    (net (code "77") (name "unconnected-(LS5D-1-Pad4)") (class "Default")
      (node (ref "LS5") (pin "4") (pinfunction "1_4") (pintype "passive"))
    )
    (net (code "78") (name "unconnected-(LS6D-1-Pad4)") (class "Default")
      (node (ref "LS6") (pin "4") (pinfunction "1_4") (pintype "passive"))
    )
    (net (code "79") (name "unconnected-(LS7D-1-Pad4)") (class "Default")
      (node (ref "LS7") (pin "4") (pinfunction "1_4") (pintype "passive"))
    )
    (net (code "80") (name "unconnected-(LS8D-1-Pad4)") (class "Default")
      (node (ref "LS8") (pin "4") (pinfunction "1_4") (pintype "passive"))
    )
    (net (code "81") (name "unconnected-(LS9D-1-Pad4)") (class "Default")
      (node (ref "LS9") (pin "4") (pinfunction "1_4") (pintype "passive"))
    )
    (net (code "82") (name "unconnected-(LS10D-1-Pad4)") (class "Default")
      (node (ref "LS10") (pin "4") (pinfunction "1_4") (pintype "passive"))
    )
    (net (code "83") (name "unconnected-(MP6500_3-EN-PadENBL)") (class "Default")
      (node (ref "MP6500_3") (pin "ENBL") (pinfunction "EN_ENBL") (pintype "bidirectional"))
    )
    (net (code "84") (name "unconnected-(MP6500_3-FLT-PadFAULT)") (class "Default")
      (node (ref "MP6500_3") (pin "FAULT") (pinfunction "FLT_FAULT") (pintype "bidirectional"))
    )
    (net (code "85") (name "unconnected-(MP6500_3-PadMS1)") (class "Default")
      (node (ref "MP6500_3") (pin "MS1") (pinfunction "MS1_MS1") (pintype "bidirectional"))
    )
    (net (code "86") (name "unconnected-(MP6500_3-PadMS2)") (class "Default")
      (node (ref "MP6500_3") (pin "MS2") (pinfunction "MS2_MS2") (pintype "bidirectional"))
    )
    (net (code "87") (name "unconnected-(MP6500_4-EN-PadENBL)") (class "Default")
      (node (ref "MP6500_4") (pin "ENBL") (pinfunction "EN_ENBL") (pintype "bidirectional"))
    )
    (net (code "88") (name "unconnected-(MP6500_4-FLT-PadFAULT)") (class "Default")
      (node (ref "MP6500_4") (pin "FAULT") (pinfunction "FLT_FAULT") (pintype "bidirectional"))
    )
    (net (code "89") (name "unconnected-(MP6500_4-PadMS1)") (class "Default")
      (node (ref "MP6500_4") (pin "MS1") (pinfunction "MS1_MS1") (pintype "bidirectional"))
    )
    (net (code "90") (name "unconnected-(MP6500_4-PadMS2)") (class "Default")
      (node (ref "MP6500_4") (pin "MS2") (pinfunction "MS2_MS2") (pintype "bidirectional"))
    )
    (net (code "91") (name "unconnected-(POT1D-1-Pad4)") (class "Default")
      (node (ref "POT1") (pin "4") (pinfunction "1_4") (pintype "passive"))
    )
    (net (code "92") (name "unconnected-(POT2D-1-Pad4)") (class "Default")
      (node (ref "POT2") (pin "4") (pinfunction "1_4") (pintype "passive"))
    )
    (net (code "93") (name "unconnected-(POT3D-1-Pad4)") (class "Default")
      (node (ref "POT3") (pin "4") (pinfunction "1_4") (pintype "passive"))
    )
    (net (code "94") (name "unconnected-(POT4D-1-Pad4)") (class "Default")
      (node (ref "POT4") (pin "4") (pinfunction "1_4") (pintype "passive"))
    )
    (net (code "95") (name "unconnected-(POT5D-1-Pad4)") (class "Default")
      (node (ref "POT5") (pin "4") (pinfunction "1_4") (pintype "passive"))
    )
    (net (code "96") (name "unconnected-(POT6D-1-Pad4)") (class "Default")
      (node (ref "POT6") (pin "4") (pinfunction "1_4") (pintype "passive"))
    )
    (net (code "97") (name "unconnected-(TBVCC1C-1-Pad3)") (class "Default")
      (node (ref "TBVCC1") (pin "3") (pinfunction "1_3") (pintype "passive"))
    )
    (net (code "98") (name "unconnected-(TBVCC1D-1-Pad4)") (class "Default")
      (node (ref "TBVCC1") (pin "4") (pinfunction "1_4") (pintype "passive"))
    )
    (net (code "99") (name "unconnected-(TBVCC2C-1-Pad3)") (class "Default")
      (node (ref "TBVCC2") (pin "3") (pinfunction "1_3") (pintype "passive"))
    )
    (net (code "100") (name "unconnected-(TBVCC2D-1-Pad4)") (class "Default")
      (node (ref "TBVCC2") (pin "4") (pinfunction "1_4") (pintype "passive"))
    )
    (net (code "101") (name "unconnected-(TBVCC3C-1-Pad3)") (class "Default")
      (node (ref "TBVCC3") (pin "3") (pinfunction "1_3") (pintype "passive"))
    )
    (net (code "102") (name "unconnected-(TBVCC3D-1-Pad4)") (class "Default")
      (node (ref "TBVCC3") (pin "4") (pinfunction "1_4") (pintype "passive"))
    )
    (net (code "103") (name "unconnected-(TBVCC4C-1-Pad3)") (class "Default")
      (node (ref "TBVCC4") (pin "3") (pinfunction "1_3") (pintype "passive"))
    )
    (net (code "104") (name "unconnected-(TBVCC4D-1-Pad4)") (class "Default")
      (node (ref "TBVCC4") (pin "4") (pinfunction "1_4") (pintype "passive"))
    )
    (net (code "105") (name "unconnected-(TEENSY4.2-Pad3V3_2)") (class "Default")
      (node (ref "TEENSY4.2") (pin "3V3_2") (pinfunction "3V3_2_3V3_2") (pintype "bidirectional"))
    )
    (net (code "106") (name "unconnected-(TEENSY4.2-Pad13{slash}SCK)") (class "Default")
      (node (ref "TEENSY4.2") (pin "13/SCK") (pinfunction "13/SCK_13/SCK") (pintype "bidirectional"))
    )
    (net (code "107") (name "unconnected-(TEENSY4.2-Pad30)") (class "Default")
      (node (ref "TEENSY4.2") (pin "30") (pinfunction "30_30") (pintype "bidirectional"))
    )
    (net (code "108") (name "unconnected-(TEENSY4.2-Pad31{slash}A12)") (class "Default")
      (node (ref "TEENSY4.2") (pin "31/A12") (pinfunction "31/A12_31/A12") (pintype "bidirectional"))
    )
    (net (code "109") (name "unconnected-(TEENSY4.2-Pad32{slash}A13)") (class "Default")
      (node (ref "TEENSY4.2") (pin "32/A13") (pinfunction "32/A13_32/A13") (pintype "bidirectional"))
    )
    (net (code "110") (name "unconnected-(TEENSY4.2-Pad33{slash}A14)") (class "Default")
      (node (ref "TEENSY4.2") (pin "33/A14") (pinfunction "33/A14_33/A14") (pintype "bidirectional"))
    )
    (net (code "111") (name "unconnected-(TEENSY4.2-Pad34{slash}A15)") (class "Default")
      (node (ref "TEENSY4.2") (pin "34/A15") (pinfunction "34/A15_34/A15") (pintype "bidirectional"))
    )
    (net (code "112") (name "unconnected-(TEENSY4.2-Pad35{slash}A16)") (class "Default")
      (node (ref "TEENSY4.2") (pin "35/A16") (pinfunction "35/A16_35/A16") (pintype "bidirectional"))
    )
    (net (code "113") (name "unconnected-(TEENSY4.2-Pad36{slash}A17)") (class "Default")
      (node (ref "TEENSY4.2") (pin "36/A17") (pinfunction "36/A17_36/A17") (pintype "bidirectional"))
    )
    (net (code "114") (name "unconnected-(TEENSY4.2-Pad37{slash}A18)") (class "Default")
      (node (ref "TEENSY4.2") (pin "37/A18") (pinfunction "37/A18_37/A18") (pintype "bidirectional"))
    )
    (net (code "115") (name "unconnected-(TEENSY4.2-PadA10)") (class "Default")
      (node (ref "TEENSY4.2") (pin "A10") (pinfunction "A10_A10") (pintype "bidirectional"))
    )
    (net (code "116") (name "unconnected-(TEENSY4.2-PadA11)") (class "Default")
      (node (ref "TEENSY4.2") (pin "A11") (pinfunction "A11_A11") (pintype "bidirectional"))
    )
    (net (code "117") (name "unconnected-(TEENSY4.2-PadAGND)") (class "Default")
      (node (ref "TEENSY4.2") (pin "AGND") (pinfunction "AGND_AGND") (pintype "bidirectional"))
    )
    (net (code "118") (name "unconnected-(TEENSY4.2-PadAREF)") (class "Default")
      (node (ref "TEENSY4.2") (pin "AREF") (pinfunction "AREF_AREF") (pintype "bidirectional"))
    )
    (net (code "119") (name "unconnected-(TEENSY4.2-PadGND2)") (class "Default")
      (node (ref "TEENSY4.2") (pin "GND2") (pinfunction "GND2_GND2") (pintype "bidirectional"))
    )
    (net (code "120") (name "unconnected-(TEENSY4.2-PadGND3)") (class "Default")
      (node (ref "TEENSY4.2") (pin "GND3") (pinfunction "GND3_GND3") (pintype "bidirectional"))
    )
    (net (code "121") (name "unconnected-(TEENSY4.2-PadPROG)") (class "Default")
      (node (ref "TEENSY4.2") (pin "PROG") (pinfunction "PROG_PROG") (pintype "bidirectional"))
    )
    (net (code "122") (name "unconnected-(TEENSY4.2-PadRESET)") (class "Default")
      (node (ref "TEENSY4.2") (pin "RESET") (pinfunction "RESET_RESET") (pintype "bidirectional"))
    )
    (net (code "123") (name "unconnected-(TEENSY4.2-PadU5V)") (class "Default")
      (node (ref "TEENSY4.2") (pin "U5V") (pinfunction "U5V_U5V") (pintype "bidirectional"))
    )
    (net (code "124") (name "unconnected-(TEENSY4.2-PadUD+)") (class "Default")
      (node (ref "TEENSY4.2") (pin "UD+") (pinfunction "UD+_UD+") (pintype "bidirectional"))
    )
    (net (code "125") (name "unconnected-(TEENSY4.2-PadUD-)") (class "Default")
      (node (ref "TEENSY4.2") (pin "UD-") (pinfunction "UD-_UD-") (pintype "bidirectional"))
    )
    (net (code "126") (name "unconnected-(TEENSY4.2-PadUGND1)") (class "Default")
      (node (ref "TEENSY4.2") (pin "UGND1") (pinfunction "UGND1_UGND1") (pintype "bidirectional"))
    )
    (net (code "127") (name "unconnected-(TEENSY4.2-PadUGND2)") (class "Default")
      (node (ref "TEENSY4.2") (pin "UGND2") (pinfunction "UGND2_UGND2") (pintype "bidirectional"))
    )
    (net (code "128") (name "unconnected-(TEENSY4.2-PadVBAT)") (class "Default")
      (node (ref "TEENSY4.2") (pin "VBAT") (pinfunction "VBAT_VBAT") (pintype "bidirectional"))
    )
    (net (code "129") (name "unconnected-(TEENSY4.2-PadVUSB)") (class "Default")
      (node (ref "TEENSY4.2") (pin "VUSB") (pinfunction "VUSB_VUSB") (pintype "bidirectional"))
    )
  )
)
